# DW1000BreakoutPeripherals.net
KiCad netlist of a schematic drawn in Altium Designer
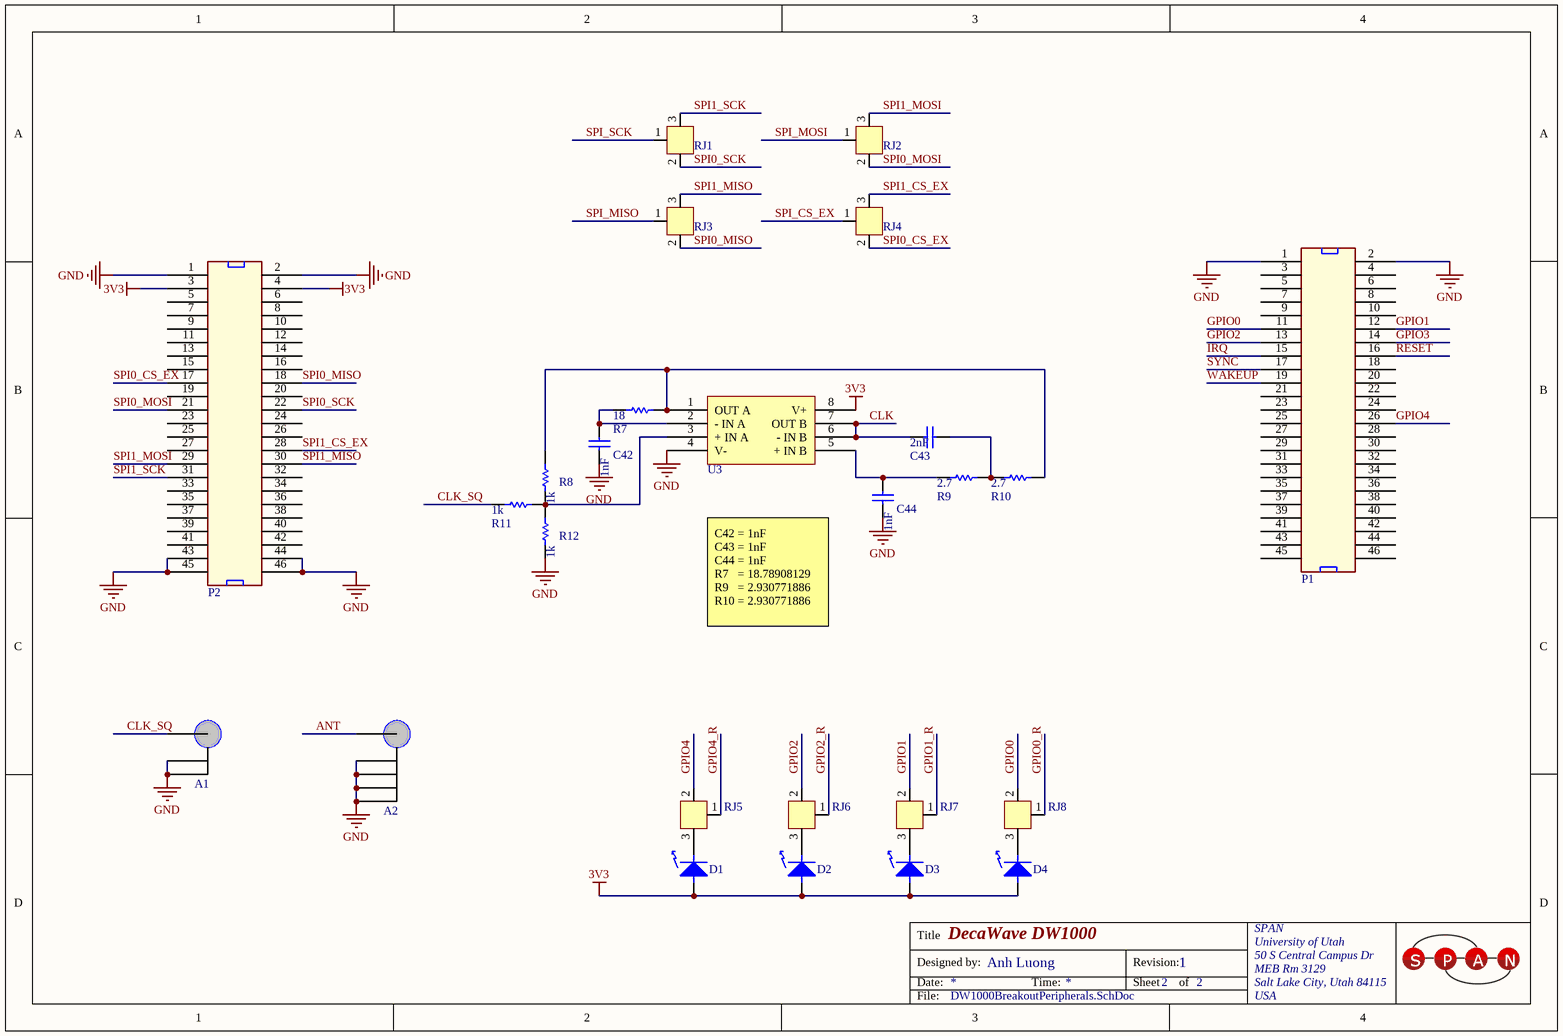
[diagram p0: DW1000BreakoutPeripherals.SchDoc]

(export (version "E")
  (design (tool "Eeschema 10.0.6"))
  (components
    (comp (ref "A1")
      (value "U.FL-R-SMT(01)")
      (footprint "U.FL-R-SMT-1")
      (description "CONN UMC JACK STR 50 OHM SMD")
      (fields (field (name "MANUFACTURER") "Hirose Electric Co Ltd"))
      (libsource (lib "DW1000Breakout") (part "U.FL-R-SMT(01)"))
    )
    (comp (ref "A2")
      (value "CONSMA003.062")
      (footprint "SMA_EDGE_MNT")
      (description "CONN SMA JACK 50 OHM EDGE MNT")
      (fields (field (name "MANUFACTURER") "Linx Technologies Inc"))
      (libsource (lib "DW1000Breakout") (part "CONSMA003.062"))
    )
    (comp (ref "C42")
      (value "GRM033R71C102KA01D")
      (footprint "CAPC1608X08N (0603)")
      (description "CAP CER 1000PF 16V 10% X7R 0201")
      (fields
        (field (name "MANUFACTURER") "Murata Electronics North America")
        (field (name "TOLERANCE") "±10%")
      )
      (libsource (lib "DW1000Breakout") (part "GRM033R71C102KA01D"))
    )
    (comp (ref "C43")
      (value "GRM1885C1H202JA01D")
      (footprint "CAPC1608X08N (0603)")
      (description "CAP CER 2000PF 50V NP0 0603")
      (fields
        (field (name "MANUFACTURER") "Murata Electronics North America")
        (field (name "TOLERANCE") "±5%")
      )
      (libsource (lib "DW1000Breakout") (part "GRM1885C1H202JA01D"))
    )
    (comp (ref "C44")
      (value "GRM033R71C102KA01D")
      (footprint "CAPC1608X08N (0603)")
      (description "CAP CER 1000PF 16V 10% X7R 0201")
      (fields
        (field (name "MANUFACTURER") "Murata Electronics North America")
        (field (name "TOLERANCE") "±10%")
      )
      (libsource (lib "DW1000Breakout") (part "GRM033R71C102KA01D"))
    )
    (comp (ref "D1")
      (value "LG Q971-KN-1")
      (footprint "CHIPLED0603")
      (description "LED CHIPLED 570NM GREEN 0603 SMD")
      (fields (field (name "MANUFACTURER") "OSRAM Opto Semiconductors Inc"))
      (libsource (lib "DWM1000Breakout") (part "LG Q971-KN-1"))
    )
    (comp (ref "D2")
      (value "LG Q971-KN-1")
      (footprint "CHIPLED0603")
      (description "LED CHIPLED 570NM GREEN 0603 SMD")
      (fields (field (name "MANUFACTURER") "OSRAM Opto Semiconductors Inc"))
      (libsource (lib "DWM1000Breakout") (part "LG Q971-KN-1"))
    )
    (comp (ref "D3")
      (value "LG Q971-KN-1")
      (footprint "CHIPLED0603")
      (description "LED CHIPLED 570NM GREEN 0603 SMD")
      (fields (field (name "MANUFACTURER") "OSRAM Opto Semiconductors Inc"))
      (libsource (lib "DWM1000Breakout") (part "LG Q971-KN-1"))
    )
    (comp (ref "D4")
      (value "LG Q971-KN-1")
      (footprint "CHIPLED0603")
      (description "LED CHIPLED 570NM GREEN 0603 SMD")
      (fields (field (name "MANUFACTURER") "OSRAM Opto Semiconductors Inc"))
      (libsource (lib "DWM1000Breakout") (part "LG Q971-KN-1"))
    )
    (comp (ref "P1")
      (value "PREC023DAAN-RC")
      (footprint "HEADER23X2")
      (description "CONN HEADER .100\" DUAL STR 46POS")
      (fields (field (name "MANUFACTURER") "Sullins Connector Solutions"))
      (libsource (lib "Chronos") (part "PREC023DAAN-RC"))
    )
    (comp (ref "P2")
      (value "PREC023DAAN-RC")
      (footprint "HEADER23X2")
      (description "CONN HEADER .100\" DUAL STR 46POS")
      (fields (field (name "MANUFACTURER") "Sullins Connector Solutions"))
      (libsource (lib "Chronos") (part "PREC023DAAN-RC"))
    )
    (comp (ref "R7")
      (value "MCR03ERTJ180")
      (footprint "RESC1608X06N (0603)")
      (description "RES SMD 18 OHM 5% 1/10W 0603")
      (fields (field (name "MANUFACTURER") "Rohm Semiconductor") (field (name "TOLERANCE") "±5%"))
      (libsource (lib "DW1000Breakout") (part "MCR03ERTJ180"))
    )
    (comp (ref "R8")
      (value "MCR03ERTJ102")
      (footprint "RESC1608X06N (0603)")
      (description "RES 1K OHM 1/10W 5% 0603 SMD")
      (fields (field (name "MANUFACTURER") "Rohm Semiconductor") (field (name "TOLERANCE") "±5%"))
      (libsource (lib "DW1000Breakout") (part "MCR03ERTJ102"))
    )
    (comp (ref "R9")
      (value "MCR03ERTJ2R7")
      (footprint "RESC1608X06N (0603)")
      (description "RES SMD 2.7 OHM 5% 1/10W 0603")
      (fields (field (name "MANUFACTURER") "Rohm Semiconductor") (field (name "TOLERANCE") "±5%"))
      (libsource (lib "DW1000Breakout") (part "MCR03ERTJ2R7"))
    )
    (comp (ref "R10")
      (value "MCR03ERTJ2R7")
      (footprint "RESC1608X06N (0603)")
      (description "RES SMD 2.7 OHM 5% 1/10W 0603")
      (fields (field (name "MANUFACTURER") "Rohm Semiconductor") (field (name "TOLERANCE") "±5%"))
      (libsource (lib "DW1000Breakout") (part "MCR03ERTJ2R7"))
    )
    (comp (ref "R11")
      (value "MCR03ERTJ102")
      (footprint "RESC1608X06N (0603)")
      (description "RES 1K OHM 1/10W 5% 0603 SMD")
      (fields (field (name "MANUFACTURER") "Rohm Semiconductor") (field (name "TOLERANCE") "±5%"))
      (libsource (lib "DW1000Breakout") (part "MCR03ERTJ102"))
    )
    (comp (ref "R12")
      (value "MCR03ERTJ102")
      (footprint "RESC1608X06N (0603)")
      (description "RES 1K OHM 1/10W 5% 0603 SMD")
      (fields (field (name "MANUFACTURER") "Rohm Semiconductor") (field (name "TOLERANCE") "±5%"))
      (libsource (lib "DW1000Breakout") (part "MCR03ERTJ102"))
    )
    (comp (ref "RJ1")
      (value "R_J")
      (footprint "RJ")
      (description "Resistor Jumper")
      (libsource (lib "") (part "R_J_1"))
    )
    (comp (ref "RJ2")
      (value "R_J")
      (footprint "RJ")
      (description "Resistor Jumper")
      (libsource (lib "") (part "R_J_1"))
    )
    (comp (ref "RJ3")
      (value "R_J")
      (footprint "RJ")
      (description "Resistor Jumper")
      (libsource (lib "") (part "R_J_1"))
    )
    (comp (ref "RJ4")
      (value "R_J")
      (footprint "RJ")
      (description "Resistor Jumper")
      (libsource (lib "") (part "R_J_1"))
    )
    (comp (ref "RJ5")
      (value "R_J")
      (footprint "RJ")
      (description "Resistor Jumper")
      (libsource (lib "DWM1000Breakout") (part "R_J"))
    )
    (comp (ref "RJ6")
      (value "R_J")
      (footprint "RJ")
      (description "Resistor Jumper")
      (libsource (lib "DWM1000Breakout") (part "R_J"))
    )
    (comp (ref "RJ7")
      (value "R_J")
      (footprint "RJ")
      (description "Resistor Jumper")
      (libsource (lib "DWM1000Breakout") (part "R_J"))
    )
    (comp (ref "RJ8")
      (value "R_J")
      (footprint "RJ")
      (description "Resistor Jumper")
      (libsource (lib "DWM1000Breakout") (part "R_J"))
    )
    (comp (ref "U3")
      (value "LMV822MM/NOPB")
      (footprint "TSOP65P490X110-8N")
      (description "Operational Amplifiers - Op Amps Low Volt Dual Op Amp")
      (fields (field (name "MANUFACTURER") "Texas Instruments"))
      (libsource (lib "DW1000Breakout") (part "LMV822MM/NOPB"))
    )
  )
  (nets
    (net (code "1") (name "/ANT") (class "Default")
      (node (ref "A2") (pin "1") (pinfunction "1_1") (pintype "passive"))
    )
    (net (code "2") (name "/CLK") (class "Default")
      (node (ref "C43") (pin "1") (pinfunction "1_1") (pintype "passive"))
      (node (ref "U3") (pin "6") (pinfunction "-_IN_B_6") (pintype "passive"))
      (node (ref "U3") (pin "7") (pinfunction "OUT_B_7") (pintype "passive"))
    )
    (net (code "3") (name "/CLK_SQ") (class "Default")
      (node (ref "A1") (pin "1") (pinfunction "1_1") (pintype "passive"))
      (node (ref "R11") (pin "1") (pinfunction "1_1") (pintype "passive"))
    )
    (net (code "4") (name "/GPIO0") (class "Default")
      (node (ref "P1") (pin "11") (pinfunction "6_11") (pintype "passive"))
      (node (ref "RJ8") (pin "2") (pinfunction "2_2") (pintype "passive"))
    )
    (net (code "5") (name "/GPIO0_R") (class "Default")
      (node (ref "RJ8") (pin "1") (pinfunction "1_1") (pintype "passive"))
    )
    (net (code "6") (name "/GPIO1") (class "Default")
      (node (ref "P1") (pin "12") (pinfunction "31_12") (pintype "passive"))
      (node (ref "RJ7") (pin "2") (pinfunction "2_2") (pintype "passive"))
    )
    (net (code "7") (name "/GPIO1_R") (class "Default")
      (node (ref "RJ7") (pin "1") (pinfunction "1_1") (pintype "passive"))
    )
    (net (code "8") (name "/GPIO2") (class "Default")
      (node (ref "P1") (pin "13") (pinfunction "7_13") (pintype "passive"))
      (node (ref "RJ6") (pin "2") (pinfunction "2_2") (pintype "passive"))
    )
    (net (code "9") (name "/GPIO2_R") (class "Default")
      (node (ref "RJ6") (pin "1") (pinfunction "1_1") (pintype "passive"))
    )
    (net (code "10") (name "/GPIO3") (class "Default")
      (node (ref "P1") (pin "14") (pinfunction "32_14") (pintype "passive"))
    )
    (net (code "11") (name "/GPIO4") (class "Default")
      (node (ref "P1") (pin "26") (pinfunction "38_26") (pintype "passive"))
      (node (ref "RJ5") (pin "2") (pinfunction "2_2") (pintype "passive"))
    )
    (net (code "12") (name "/GPIO4_R") (class "Default")
      (node (ref "RJ5") (pin "1") (pinfunction "1_1") (pintype "passive"))
    )
    (net (code "13") (name "/IRQ") (class "Default")
      (node (ref "P1") (pin "15") (pinfunction "8_15") (pintype "passive"))
    )
    (net (code "14") (name "/RESET") (class "Default")
      (node (ref "P1") (pin "16") (pinfunction "33_16") (pintype "passive"))
    )
    (net (code "15") (name "/SPI0_CS_EX") (class "Default")
      (node (ref "P2") (pin "17") (pinfunction "9_17") (pintype "passive"))
      (node (ref "RJ4") (pin "2") (pinfunction "2_2") (pintype "passive"))
    )
    (net (code "16") (name "/SPI0_MISO") (class "Default")
      (node (ref "P2") (pin "18") (pinfunction "34_18") (pintype "passive"))
      (node (ref "RJ3") (pin "2") (pinfunction "2_2") (pintype "passive"))
    )
    (net (code "17") (name "/SPI0_MOSI") (class "Default")
      (node (ref "P2") (pin "21") (pinfunction "11_21") (pintype "passive"))
      (node (ref "RJ2") (pin "2") (pinfunction "2_2") (pintype "passive"))
    )
    (net (code "18") (name "/SPI0_SCK") (class "Default")
      (node (ref "P2") (pin "22") (pinfunction "36_22") (pintype "passive"))
      (node (ref "RJ1") (pin "2") (pinfunction "2_2") (pintype "passive"))
    )
    (net (code "19") (name "/SPI1_CS_EX") (class "Default")
      (node (ref "P2") (pin "28") (pinfunction "39_28") (pintype "passive"))
      (node (ref "RJ4") (pin "3") (pinfunction "3_3") (pintype "passive"))
    )
    (net (code "20") (name "/SPI1_MISO") (class "Default")
      (node (ref "P2") (pin "30") (pinfunction "40_30") (pintype "passive"))
      (node (ref "RJ3") (pin "3") (pinfunction "3_3") (pintype "passive"))
    )
    (net (code "21") (name "/SPI1_MOSI") (class "Default")
      (node (ref "P2") (pin "29") (pinfunction "15_29") (pintype "passive"))
      (node (ref "RJ2") (pin "3") (pinfunction "3_3") (pintype "passive"))
    )
    (net (code "22") (name "/SPI1_SCK") (class "Default")
      (node (ref "P2") (pin "31") (pinfunction "16_31") (pintype "passive"))
      (node (ref "RJ1") (pin "3") (pinfunction "3_3") (pintype "passive"))
    )
    (net (code "23") (name "/SPI_CS_EX") (class "Default")
      (node (ref "RJ4") (pin "1") (pinfunction "1_1") (pintype "passive"))
    )
    (net (code "24") (name "/SPI_MISO") (class "Default")
      (node (ref "RJ3") (pin "1") (pinfunction "1_1") (pintype "passive"))
    )
    (net (code "25") (name "/SPI_MOSI") (class "Default")
      (node (ref "RJ2") (pin "1") (pinfunction "1_1") (pintype "passive"))
    )
    (net (code "26") (name "/SPI_SCK") (class "Default")
      (node (ref "RJ1") (pin "1") (pinfunction "1_1") (pintype "passive"))
    )
    (net (code "27") (name "/SYNC") (class "Default")
      (node (ref "P1") (pin "17") (pinfunction "9_17") (pintype "passive"))
    )
    (net (code "28") (name "/WAKEUP") (class "Default")
      (node (ref "P1") (pin "19") (pinfunction "10_19") (pintype "passive"))
    )
    (net (code "29") (name "3V3") (class "Default")
      (node (ref "D1") (pin "1") (pinfunction "1_1") (pintype "passive"))
      (node (ref "D2") (pin "1") (pinfunction "1_1") (pintype "passive"))
      (node (ref "D3") (pin "1") (pinfunction "1_1") (pintype "passive"))
      (node (ref "D4") (pin "1") (pinfunction "1_1") (pintype "passive"))
      (node (ref "P2") (pin "3") (pinfunction "2_3") (pintype "passive"))
      (node (ref "P2") (pin "4") (pinfunction "27_4") (pintype "passive"))
      (node (ref "U3") (pin "8") (pinfunction "V+_8") (pintype "passive"))
    )
    (net (code "30") (name "GND") (class "Default")
      (node (ref "A1") (pin "2") (pinfunction "2_2") (pintype "passive"))
      (node (ref "A1") (pin "3") (pinfunction "3_3") (pintype "passive"))
      (node (ref "A2") (pin "2") (pinfunction "2_2") (pintype "passive"))
      (node (ref "A2") (pin "3") (pinfunction "3_3") (pintype "passive"))
      (node (ref "A2") (pin "4") (pinfunction "4_4") (pintype "passive"))
      (node (ref "A2") (pin "5") (pinfunction "5_5") (pintype "passive"))
      (node (ref "C42") (pin "1") (pinfunction "1_1") (pintype "passive"))
      (node (ref "C44") (pin "1") (pinfunction "1_1") (pintype "passive"))
      (node (ref "P1") (pin "1") (pinfunction "1_1") (pintype "passive"))
      (node (ref "P1") (pin "2") (pinfunction "26_2") (pintype "passive"))
      (node (ref "P2") (pin "1") (pinfunction "1_1") (pintype "passive"))
      (node (ref "P2") (pin "2") (pinfunction "26_2") (pintype "passive"))
      (node (ref "P2") (pin "43") (pinfunction "22_43") (pintype "passive"))
      (node (ref "P2") (pin "44") (pinfunction "47_44") (pintype "passive"))
      (node (ref "P2") (pin "45") (pinfunction "23_45") (pintype "passive"))
      (node (ref "P2") (pin "46") (pinfunction "48_46") (pintype "passive"))
      (node (ref "R12") (pin "1") (pinfunction "1_1") (pintype "passive"))
      (node (ref "U3") (pin "4") (pinfunction "V-_4") (pintype "passive"))
    )
    (net (code "31") (name "Net-(C43-Pad2)") (class "Default")
      (node (ref "C43") (pin "2") (pinfunction "2_2") (pintype "passive"))
      (node (ref "R10") (pin "1") (pinfunction "1_1") (pintype "passive"))
      (node (ref "R9") (pin "2") (pinfunction "2_2") (pintype "passive"))
    )
    (net (code "32") (name "Net-(D1-Pad2)") (class "Default")
      (node (ref "D1") (pin "2") (pinfunction "2_2") (pintype "passive"))
      (node (ref "RJ5") (pin "3") (pinfunction "3_3") (pintype "passive"))
    )
    (net (code "33") (name "Net-(D2-Pad2)") (class "Default")
      (node (ref "D2") (pin "2") (pinfunction "2_2") (pintype "passive"))
      (node (ref "RJ6") (pin "3") (pinfunction "3_3") (pintype "passive"))
    )
    (net (code "34") (name "Net-(D3-Pad2)") (class "Default")
      (node (ref "D3") (pin "2") (pinfunction "2_2") (pintype "passive"))
      (node (ref "RJ7") (pin "3") (pinfunction "3_3") (pintype "passive"))
    )
    (net (code "35") (name "Net-(D4-Pad2)") (class "Default")
      (node (ref "D4") (pin "2") (pinfunction "2_2") (pintype "passive"))
      (node (ref "RJ8") (pin "3") (pinfunction "3_3") (pintype "passive"))
    )
    (net (code "36") (name "Net-(U3-+_IN_A)") (class "Default")
      (node (ref "R11") (pin "2") (pinfunction "2_2") (pintype "passive"))
      (node (ref "R12") (pin "2") (pinfunction "2_2") (pintype "passive"))
      (node (ref "R8") (pin "1") (pinfunction "1_1") (pintype "passive"))
      (node (ref "U3") (pin "3") (pinfunction "+_IN_A_3") (pintype "passive"))
    )
    (net (code "37") (name "Net-(U3-+_IN_B)") (class "Default")
      (node (ref "C44") (pin "2") (pinfunction "2_2") (pintype "passive"))
      (node (ref "R9") (pin "1") (pinfunction "1_1") (pintype "passive"))
      (node (ref "U3") (pin "5") (pinfunction "+_IN_B_5") (pintype "passive"))
    )
    (net (code "38") (name "Net-(U3--_IN_A)") (class "Default")
      (node (ref "C42") (pin "2") (pinfunction "2_2") (pintype "passive"))
      (node (ref "R7") (pin "1") (pinfunction "1_1") (pintype "passive"))
      (node (ref "U3") (pin "2") (pinfunction "-_IN_A_2") (pintype "passive"))
    )
    (net (code "39") (name "Net-(U3-OUT_A)") (class "Default")
      (node (ref "R10") (pin "2") (pinfunction "2_2") (pintype "passive"))
      (node (ref "R7") (pin "2") (pinfunction "2_2") (pintype "passive"))
      (node (ref "R8") (pin "2") (pinfunction "2_2") (pintype "passive"))
      (node (ref "U3") (pin "1") (pinfunction "OUT_A_1") (pintype "passive"))
    )
    (net (code "40") (name "unconnected-(P1-2-Pad3)") (class "Default")
      (node (ref "P1") (pin "3") (pinfunction "2_3") (pintype "passive"))
    )
    (net (code "41") (name "unconnected-(P1-3-Pad5)") (class "Default")
      (node (ref "P1") (pin "5") (pinfunction "3_5") (pintype "passive"))
    )
    (net (code "42") (name "unconnected-(P1-4-Pad7)") (class "Default")
      (node (ref "P1") (pin "7") (pinfunction "4_7") (pintype "passive"))
    )
    (net (code "43") (name "unconnected-(P1-5-Pad9)") (class "Default")
      (node (ref "P1") (pin "9") (pinfunction "5_9") (pintype "passive"))
    )
    (net (code "44") (name "unconnected-(P1-11-Pad21)") (class "Default")
      (node (ref "P1") (pin "21") (pinfunction "11_21") (pintype "passive"))
    )
    (net (code "45") (name "unconnected-(P1-12-Pad23)") (class "Default")
      (node (ref "P1") (pin "23") (pinfunction "12_23") (pintype "passive"))
    )
    (net (code "46") (name "unconnected-(P1-13-Pad25)") (class "Default")
      (node (ref "P1") (pin "25") (pinfunction "13_25") (pintype "passive"))
    )
    (net (code "47") (name "unconnected-(P1-14-Pad27)") (class "Default")
      (node (ref "P1") (pin "27") (pinfunction "14_27") (pintype "passive"))
    )
    (net (code "48") (name "unconnected-(P1-15-Pad29)") (class "Default")
      (node (ref "P1") (pin "29") (pinfunction "15_29") (pintype "passive"))
    )
    (net (code "49") (name "unconnected-(P1-16-Pad31)") (class "Default")
      (node (ref "P1") (pin "31") (pinfunction "16_31") (pintype "passive"))
    )
    (net (code "50") (name "unconnected-(P1-17-Pad33)") (class "Default")
      (node (ref "P1") (pin "33") (pinfunction "17_33") (pintype "passive"))
    )
    (net (code "51") (name "unconnected-(P1-18-Pad35)") (class "Default")
      (node (ref "P1") (pin "35") (pinfunction "18_35") (pintype "passive"))
    )
    (net (code "52") (name "unconnected-(P1-19-Pad37)") (class "Default")
      (node (ref "P1") (pin "37") (pinfunction "19_37") (pintype "passive"))
    )
    (net (code "53") (name "unconnected-(P1-20-Pad39)") (class "Default")
      (node (ref "P1") (pin "39") (pinfunction "20_39") (pintype "passive"))
    )
    (net (code "54") (name "unconnected-(P1-21-Pad41)") (class "Default")
      (node (ref "P1") (pin "41") (pinfunction "21_41") (pintype "passive"))
    )
    (net (code "55") (name "unconnected-(P1-22-Pad43)") (class "Default")
      (node (ref "P1") (pin "43") (pinfunction "22_43") (pintype "passive"))
    )
    (net (code "56") (name "unconnected-(P1-23-Pad45)") (class "Default")
      (node (ref "P1") (pin "45") (pinfunction "23_45") (pintype "passive"))
    )
    (net (code "57") (name "unconnected-(P1-27-Pad4)") (class "Default")
      (node (ref "P1") (pin "4") (pinfunction "27_4") (pintype "passive"))
    )
    (net (code "58") (name "unconnected-(P1-28-Pad6)") (class "Default")
      (node (ref "P1") (pin "6") (pinfunction "28_6") (pintype "passive"))
    )
    (net (code "59") (name "unconnected-(P1-29-Pad8)") (class "Default")
      (node (ref "P1") (pin "8") (pinfunction "29_8") (pintype "passive"))
    )
    (net (code "60") (name "unconnected-(P1-30-Pad10)") (class "Default")
      (node (ref "P1") (pin "10") (pinfunction "30_10") (pintype "passive"))
    )
    (net (code "61") (name "unconnected-(P1-34-Pad18)") (class "Default")
      (node (ref "P1") (pin "18") (pinfunction "34_18") (pintype "passive"))
    )
    (net (code "62") (name "unconnected-(P1-35-Pad20)") (class "Default")
      (node (ref "P1") (pin "20") (pinfunction "35_20") (pintype "passive"))
    )
    (net (code "63") (name "unconnected-(P1-36-Pad22)") (class "Default")
      (node (ref "P1") (pin "22") (pinfunction "36_22") (pintype "passive"))
    )
    (net (code "64") (name "unconnected-(P1-37-Pad24)") (class "Default")
      (node (ref "P1") (pin "24") (pinfunction "37_24") (pintype "passive"))
    )
    (net (code "65") (name "unconnected-(P1-39-Pad28)") (class "Default")
      (node (ref "P1") (pin "28") (pinfunction "39_28") (pintype "passive"))
    )
    (net (code "66") (name "unconnected-(P1-40-Pad30)") (class "Default")
      (node (ref "P1") (pin "30") (pinfunction "40_30") (pintype "passive"))
    )
    (net (code "67") (name "unconnected-(P1-41-Pad32)") (class "Default")
      (node (ref "P1") (pin "32") (pinfunction "41_32") (pintype "passive"))
    )
    (net (code "68") (name "unconnected-(P1-42-Pad34)") (class "Default")
      (node (ref "P1") (pin "34") (pinfunction "42_34") (pintype "passive"))
    )
    (net (code "69") (name "unconnected-(P1-43-Pad36)") (class "Default")
      (node (ref "P1") (pin "36") (pinfunction "43_36") (pintype "passive"))
    )
    (net (code "70") (name "unconnected-(P1-44-Pad38)") (class "Default")
      (node (ref "P1") (pin "38") (pinfunction "44_38") (pintype "passive"))
    )
    (net (code "71") (name "unconnected-(P1-45-Pad40)") (class "Default")
      (node (ref "P1") (pin "40") (pinfunction "45_40") (pintype "passive"))
    )
    (net (code "72") (name "unconnected-(P1-46-Pad42)") (class "Default")
      (node (ref "P1") (pin "42") (pinfunction "46_42") (pintype "passive"))
    )
    (net (code "73") (name "unconnected-(P1-47-Pad44)") (class "Default")
      (node (ref "P1") (pin "44") (pinfunction "47_44") (pintype "passive"))
    )
    (net (code "74") (name "unconnected-(P1-48-Pad46)") (class "Default")
      (node (ref "P1") (pin "46") (pinfunction "48_46") (pintype "passive"))
    )
    (net (code "75") (name "unconnected-(P2-3-Pad5)") (class "Default")
      (node (ref "P2") (pin "5") (pinfunction "3_5") (pintype "passive"))
    )
    (net (code "76") (name "unconnected-(P2-4-Pad7)") (class "Default")
      (node (ref "P2") (pin "7") (pinfunction "4_7") (pintype "passive"))
    )
    (net (code "77") (name "unconnected-(P2-5-Pad9)") (class "Default")
      (node (ref "P2") (pin "9") (pinfunction "5_9") (pintype "passive"))
    )
    (net (code "78") (name "unconnected-(P2-6-Pad11)") (class "Default")
      (node (ref "P2") (pin "11") (pinfunction "6_11") (pintype "passive"))
    )
    (net (code "79") (name "unconnected-(P2-7-Pad13)") (class "Default")
      (node (ref "P2") (pin "13") (pinfunction "7_13") (pintype "passive"))
    )
    (net (code "80") (name "unconnected-(P2-8-Pad15)") (class "Default")
      (node (ref "P2") (pin "15") (pinfunction "8_15") (pintype "passive"))
    )
    (net (code "81") (name "unconnected-(P2-10-Pad19)") (class "Default")
      (node (ref "P2") (pin "19") (pinfunction "10_19") (pintype "passive"))
    )
    (net (code "82") (name "unconnected-(P2-12-Pad23)") (class "Default")
      (node (ref "P2") (pin "23") (pinfunction "12_23") (pintype "passive"))
    )
    (net (code "83") (name "unconnected-(P2-13-Pad25)") (class "Default")
      (node (ref "P2") (pin "25") (pinfunction "13_25") (pintype "passive"))
    )
    (net (code "84") (name "unconnected-(P2-14-Pad27)") (class "Default")
      (node (ref "P2") (pin "27") (pinfunction "14_27") (pintype "passive"))
    )
    (net (code "85") (name "unconnected-(P2-17-Pad33)") (class "Default")
      (node (ref "P2") (pin "33") (pinfunction "17_33") (pintype "passive"))
    )
    (net (code "86") (name "unconnected-(P2-18-Pad35)") (class "Default")
      (node (ref "P2") (pin "35") (pinfunction "18_35") (pintype "passive"))
    )
    (net (code "87") (name "unconnected-(P2-19-Pad37)") (class "Default")
      (node (ref "P2") (pin "37") (pinfunction "19_37") (pintype "passive"))
    )
    (net (code "88") (name "unconnected-(P2-20-Pad39)") (class "Default")
      (node (ref "P2") (pin "39") (pinfunction "20_39") (pintype "passive"))
    )
    (net (code "89") (name "unconnected-(P2-21-Pad41)") (class "Default")
      (node (ref "P2") (pin "41") (pinfunction "21_41") (pintype "passive"))
    )
    (net (code "90") (name "unconnected-(P2-28-Pad6)") (class "Default")
      (node (ref "P2") (pin "6") (pinfunction "28_6") (pintype "passive"))
    )
    (net (code "91") (name "unconnected-(P2-29-Pad8)") (class "Default")
      (node (ref "P2") (pin "8") (pinfunction "29_8") (pintype "passive"))
    )
    (net (code "92") (name "unconnected-(P2-30-Pad10)") (class "Default")
      (node (ref "P2") (pin "10") (pinfunction "30_10") (pintype "passive"))
    )
    (net (code "93") (name "unconnected-(P2-31-Pad12)") (class "Default")
      (node (ref "P2") (pin "12") (pinfunction "31_12") (pintype "passive"))
    )
    (net (code "94") (name "unconnected-(P2-32-Pad14)") (class "Default")
      (node (ref "P2") (pin "14") (pinfunction "32_14") (pintype "passive"))
    )
    (net (code "95") (name "unconnected-(P2-33-Pad16)") (class "Default")
      (node (ref "P2") (pin "16") (pinfunction "33_16") (pintype "passive"))
    )
    (net (code "96") (name "unconnected-(P2-35-Pad20)") (class "Default")
      (node (ref "P2") (pin "20") (pinfunction "35_20") (pintype "passive"))
    )
    (net (code "97") (name "unconnected-(P2-37-Pad24)") (class "Default")
      (node (ref "P2") (pin "24") (pinfunction "37_24") (pintype "passive"))
    )
    (net (code "98") (name "unconnected-(P2-38-Pad26)") (class "Default")
      (node (ref "P2") (pin "26") (pinfunction "38_26") (pintype "passive"))
    )
    (net (code "99") (name "unconnected-(P2-41-Pad32)") (class "Default")
      (node (ref "P2") (pin "32") (pinfunction "41_32") (pintype "passive"))
    )
    (net (code "100") (name "unconnected-(P2-42-Pad34)") (class "Default")
      (node (ref "P2") (pin "34") (pinfunction "42_34") (pintype "passive"))
    )
    (net (code "101") (name "unconnected-(P2-43-Pad36)") (class "Default")
      (node (ref "P2") (pin "36") (pinfunction "43_36") (pintype "passive"))
    )
    (net (code "102") (name "unconnected-(P2-44-Pad38)") (class "Default")
      (node (ref "P2") (pin "38") (pinfunction "44_38") (pintype "passive"))
    )
    (net (code "103") (name "unconnected-(P2-45-Pad40)") (class "Default")
      (node (ref "P2") (pin "40") (pinfunction "45_40") (pintype "passive"))
    )
    (net (code "104") (name "unconnected-(P2-46-Pad42)") (class "Default")
      (node (ref "P2") (pin "42") (pinfunction "46_42") (pintype "passive"))
    )
  )
)
